# SignalAdapter.net
KiCad netlist of a schematic drawn in Altium Designer
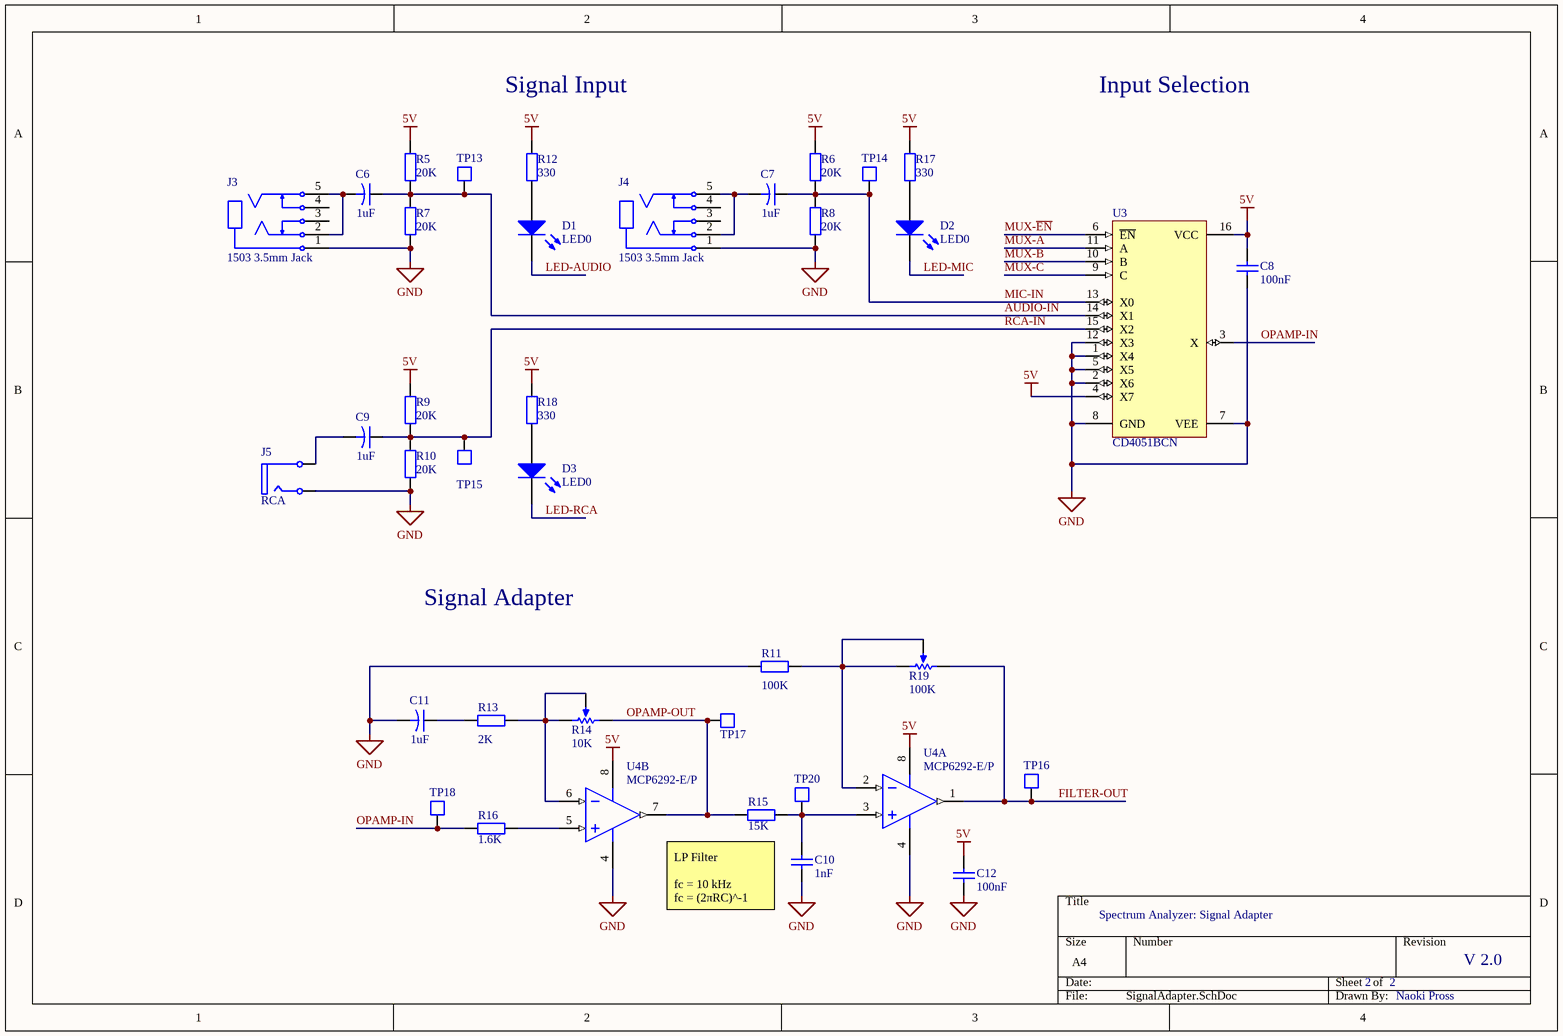
[diagram p0: SignalAdapter.SchDoc]

(export (version "E")
  (design (tool "Eeschema 10.0.6"))
  (components
    (comp (ref "C6")
      (value "1uF")
      (footprint "CAPR5-4X5")
      (description "Capacitor")
      (fields (field (name "Comment") "Cap2") (field (name "PUBLISHER") "Altium Limited"))
      (libsource (lib "Miscellaneous Devices") (part "Cap2"))
    )
    (comp (ref "C7")
      (value "1uF")
      (footprint "CAPR5-4X5")
      (description "Capacitor")
      (fields (field (name "Comment") "Cap2") (field (name "PUBLISHER") "Altium Limited"))
      (libsource (lib "Miscellaneous Devices") (part "Cap2"))
    )
    (comp (ref "C8")
      (value "100nF")
      (footprint "RAD-0.1")
      (description "Capacitor")
      (fields (field (name "Comment") "Cap") (field (name "PUBLISHER") "Altium Limited"))
      (libsource (lib "Miscellaneous Devices") (part "Cap"))
    )
    (comp (ref "C9")
      (value "1uF")
      (footprint "CAPR5-4X5")
      (description "Capacitor")
      (fields (field (name "Comment") "Cap2") (field (name "PUBLISHER") "Altium Limited"))
      (libsource (lib "Miscellaneous Devices") (part "Cap2"))
    )
    (comp (ref "C10")
      (value "1nF")
      (footprint "RAD-0.1")
      (description "Capacitor")
      (fields (field (name "Comment") "Cap") (field (name "PUBLISHER") "Altium Limited"))
      (libsource (lib "Miscellaneous Devices") (part "Cap"))
    )
    (comp (ref "C11")
      (value "1uF")
      (footprint "CAPR5-4X5")
      (description "Capacitor")
      (fields (field (name "Comment") "Cap2") (field (name "PUBLISHER") "Altium Limited"))
      (libsource (lib "Miscellaneous Devices") (part "Cap2"))
    )
    (comp (ref "C12")
      (value "100nF")
      (footprint "RAD-0.1")
      (description "Capacitor")
      (fields (field (name "Comment") "Cap") (field (name "PUBLISHER") "Altium Limited"))
      (libsource (lib "Miscellaneous Devices") (part "Cap"))
    )
    (comp (ref "D1")
      (value "LED0")
      (footprint "LED-0")
      (description "Typical INFRARED GaAs LED")
      (fields (field (name "PUBLISHER") "Altium Limited"))
      (libsource (lib "Miscellaneous Devices") (part "LED0"))
    )
    (comp (ref "D2")
      (value "LED0")
      (footprint "LED-0")
      (description "Typical INFRARED GaAs LED")
      (fields (field (name "PUBLISHER") "Altium Limited"))
      (libsource (lib "Miscellaneous Devices") (part "LED0"))
    )
    (comp (ref "D3")
      (value "LED0")
      (footprint "LED-0")
      (description "Typical INFRARED GaAs LED")
      (fields (field (name "PUBLISHER") "Altium Limited"))
      (libsource (lib "Miscellaneous Devices") (part "LED0"))
    )
    (comp (ref "J3")
      (value "1503 3.5mm Jack")
      (footprint "Lumberg-Connectors:JIS C 6560")
      (description "1503 09/17 Jack connector")
      (libsource (lib "lumberg-connectors") (part "1503"))
    )
    (comp (ref "J4")
      (value "1503 3.5mm Jack")
      (footprint "Lumberg-Connectors:JIS C 6560")
      (description "1503 09/17 Jack connector")
      (libsource (lib "lumberg-connectors") (part "1503"))
    )
    (comp (ref "J5")
      (value "RCA")
      (footprint "Lumberg-Connectors:RC-5231")
      (description "RCA Phono Jack, Right Angle, Thru-Hole, Snap-In")
      (fields (field (name "PUBLISHER") "Altium Limited"))
      (libsource (lib "Miscellaneous Connectors") (part "RCA"))
    )
    (comp (ref "R5")
      (value "20K")
      (footprint "AXIAL-0.4")
      (description "Resistor")
      (fields (field (name "Comment") "Res2") (field (name "PUBLISHER") "Altium Limited"))
      (libsource (lib "Miscellaneous Devices") (part "Res2"))
    )
    (comp (ref "R6")
      (value "20K")
      (footprint "AXIAL-0.4")
      (description "Resistor")
      (fields (field (name "Comment") "Res2") (field (name "PUBLISHER") "Altium Limited"))
      (libsource (lib "Miscellaneous Devices") (part "Res2"))
    )
    (comp (ref "R7")
      (value "20K")
      (footprint "AXIAL-0.4")
      (description "Resistor")
      (fields (field (name "Comment") "Res2") (field (name "PUBLISHER") "Altium Limited"))
      (libsource (lib "Miscellaneous Devices") (part "Res2"))
    )
    (comp (ref "R8")
      (value "20K")
      (footprint "AXIAL-0.4")
      (description "Resistor")
      (fields (field (name "Comment") "Res2") (field (name "PUBLISHER") "Altium Limited"))
      (libsource (lib "Miscellaneous Devices") (part "Res2"))
    )
    (comp (ref "R9")
      (value "20K")
      (footprint "AXIAL-0.4")
      (description "Resistor")
      (fields (field (name "Comment") "Res2") (field (name "PUBLISHER") "Altium Limited"))
      (libsource (lib "Miscellaneous Devices") (part "Res2"))
    )
    (comp (ref "R10")
      (value "20K")
      (footprint "AXIAL-0.4")
      (description "Resistor")
      (fields (field (name "Comment") "Res2") (field (name "PUBLISHER") "Altium Limited"))
      (libsource (lib "Miscellaneous Devices") (part "Res2"))
    )
    (comp (ref "R11")
      (value "100K")
      (footprint "AXIAL-0.4")
      (description "Resistor")
      (fields (field (name "Comment") "Res2") (field (name "PUBLISHER") "Altium Limited"))
      (libsource (lib "") (part "Res2_2"))
    )
    (comp (ref "R12")
      (value "330")
      (footprint "AXIAL-0.4")
      (description "Resistor")
      (fields (field (name "Comment") "Res2") (field (name "PUBLISHER") "Altium Limited"))
      (libsource (lib "Miscellaneous Devices") (part "Res2"))
    )
    (comp (ref "R13")
      (value "2K")
      (footprint "AXIAL-0.4")
      (description "Resistor")
      (fields (field (name "Comment") "Res2") (field (name "PUBLISHER") "Altium Limited"))
      (libsource (lib "") (part "Res2_2"))
    )
    (comp (ref "R14")
      (value "10K")
      (footprint "VR4")
      (description "Potentiometer")
      (fields (field (name "Comment") "RPot") (field (name "PUBLISHER") "Altium Limited"))
      (libsource (lib "Miscellaneous Devices") (part "RPot"))
    )
    (comp (ref "R15")
      (value "15K")
      (footprint "AXIAL-0.4")
      (description "Resistor")
      (fields (field (name "Comment") "Res2") (field (name "PUBLISHER") "Altium Limited"))
      (libsource (lib "") (part "Res2_1"))
    )
    (comp (ref "R16")
      (value "1.6K")
      (footprint "AXIAL-0.4")
      (description "Resistor")
      (fields (field (name "Comment") "Res2") (field (name "PUBLISHER") "Altium Limited"))
      (libsource (lib "") (part "Res2_1"))
    )
    (comp (ref "R17")
      (value "330")
      (footprint "AXIAL-0.4")
      (description "Resistor")
      (fields (field (name "Comment") "Res2") (field (name "PUBLISHER") "Altium Limited"))
      (libsource (lib "Miscellaneous Devices") (part "Res2"))
    )
    (comp (ref "R18")
      (value "330")
      (footprint "AXIAL-0.4")
      (description "Resistor")
      (fields (field (name "Comment") "Res2") (field (name "PUBLISHER") "Altium Limited"))
      (libsource (lib "Miscellaneous Devices") (part "Res2"))
    )
    (comp (ref "R19")
      (value "100K")
      (footprint "VR4")
      (description "Potentiometer")
      (fields (field (name "Comment") "RPot") (field (name "PUBLISHER") "Altium Limited"))
      (libsource (lib "Miscellaneous Devices") (part "RPot"))
    )
    (comp (ref "TP13") (value "Test Pad") (footprint "PIN1") (libsource (lib "TestPad") (part "TestPad")))
    (comp (ref "TP14") (value "Test Pad") (footprint "PIN1") (libsource (lib "TestPad") (part "TestPad")))
    (comp (ref "TP15") (value "Test Pad") (footprint "PIN1") (libsource (lib "TestPad") (part "TestPad")))
    (comp (ref "TP16") (value "Test Pad") (footprint "PIN1") (libsource (lib "TestPad") (part "TestPad")))
    (comp (ref "TP17") (value "Test Pad") (footprint "PIN1") (libsource (lib "TestPad") (part "TestPad")))
    (comp (ref "TP18") (value "Test Pad") (footprint "PIN1") (libsource (lib "TestPad") (part "TestPad")))
    (comp (ref "TP20") (value "Test Pad") (footprint "PIN1") (libsource (lib "TestPad") (part "TestPad")))
    (comp (ref "U3")
      (value "CD4051BCN")
      (footprint "N16E")
      (description "8-Channel Analog Multiplexer/Demultiplexer")
      (fields (field (name "PUBLISHER") "Altium Limited"))
      (libsource (lib "FSC Logic Multiplexer") (part "CD4051BCN"))
    )
    (comp (ref "U4")
      (value "MCP6292-E/P")
      (footprint "PDIP300-P8")
      (description "1.0 mA, 10 MHz Rail-to-Rail Operational Amplifier, 8-Pin PDIP, Extended Temperature")
      (fields (field (name "PUBLISHER") "Altium Limited"))
      (libsource (lib "Microchip Linear Devices") (part "MCP6292-E/P"))
    )
  )
  (nets
    (net (code "1") (name "/AUDIO-IN") (class "Default")
      (node (ref "C6") (pin "1") (pinfunction "1_1") (pintype "passive"))
      (node (ref "R5") (pin "1") (pinfunction "1_1") (pintype "passive"))
      (node (ref "R7") (pin "2") (pinfunction "2_2") (pintype "passive"))
      (node (ref "TP13") (pin "1") (pinfunction "1_1") (pintype "passive"))
      (node (ref "U3") (pin "14") (pinfunction "X1_14") (pintype "bidirectional"))
    )
    (net (code "2") (name "/FILTER-OUT") (class "Default")
      (node (ref "R19") (pin "1") (pinfunction "TOP_1") (pintype "passive"))
      (node (ref "TP16") (pin "1") (pinfunction "1_1") (pintype "passive"))
      (node (ref "U4") (pin "1") (pinfunction "VOUTA_1") (pintype "output"))
    )
    (net (code "3") (name "/LED-AUDIO") (class "Default")
      (node (ref "D1") (pin "2") (pinfunction "K_2") (pintype "passive"))
    )
    (net (code "4") (name "/LED-MIC") (class "Default")
      (node (ref "D2") (pin "2") (pinfunction "K_2") (pintype "passive"))
    )
    (net (code "5") (name "/LED-RCA") (class "Default")
      (node (ref "D3") (pin "2") (pinfunction "K_2") (pintype "passive"))
    )
    (net (code "6") (name "/MIC-IN") (class "Default")
      (node (ref "C7") (pin "1") (pinfunction "1_1") (pintype "passive"))
      (node (ref "R6") (pin "1") (pinfunction "1_1") (pintype "passive"))
      (node (ref "R8") (pin "2") (pinfunction "2_2") (pintype "passive"))
      (node (ref "TP14") (pin "1") (pinfunction "1_1") (pintype "passive"))
      (node (ref "U3") (pin "13") (pinfunction "X0_13") (pintype "bidirectional"))
    )
    (net (code "7") (name "/MUX-A") (class "Default")
      (node (ref "U3") (pin "11") (pinfunction "A_11") (pintype "input"))
    )
    (net (code "8") (name "/MUX-B") (class "Default")
      (node (ref "U3") (pin "10") (pinfunction "B_10") (pintype "input"))
    )
    (net (code "9") (name "/MUX-C") (class "Default")
      (node (ref "U3") (pin "9") (pinfunction "C_9") (pintype "input"))
    )
    (net (code "10") (name "/MUX-~{EN}") (class "Default")
      (node (ref "U3") (pin "6") (pinfunction "~{EN}_6") (pintype "input"))
    )
    (net (code "11") (name "/OPAMP-IN") (class "Default")
      (node (ref "R16") (pin "2") (pinfunction "2_2") (pintype "passive"))
      (node (ref "TP18") (pin "1") (pinfunction "1_1") (pintype "passive"))
      (node (ref "U3") (pin "3") (pinfunction "X_3") (pintype "bidirectional"))
    )
    (net (code "12") (name "/OPAMP-OUT") (class "Default")
      (node (ref "R14") (pin "1") (pinfunction "TOP_1") (pintype "passive"))
      (node (ref "R15") (pin "2") (pinfunction "2_2") (pintype "passive"))
      (node (ref "TP17") (pin "1") (pinfunction "1_1") (pintype "passive"))
      (node (ref "U4") (pin "7") (pinfunction "VOUTB_7") (pintype "output"))
    )
    (net (code "13") (name "/RCA-IN") (class "Default")
      (node (ref "C9") (pin "1") (pinfunction "1_1") (pintype "passive"))
      (node (ref "R10") (pin "2") (pinfunction "2_2") (pintype "passive"))
      (node (ref "R9") (pin "1") (pinfunction "1_1") (pintype "passive"))
      (node (ref "TP15") (pin "1") (pinfunction "1_1") (pintype "passive"))
      (node (ref "U3") (pin "15") (pinfunction "X2_15") (pintype "bidirectional"))
    )
    (net (code "14") (name "5V") (class "Default")
      (node (ref "C12") (pin "1") (pinfunction "1_1") (pintype "passive"))
      (node (ref "C8") (pin "1") (pinfunction "1_1") (pintype "passive"))
      (node (ref "R12") (pin "2") (pinfunction "2_2") (pintype "passive"))
      (node (ref "R17") (pin "2") (pinfunction "2_2") (pintype "passive"))
      (node (ref "R18") (pin "2") (pinfunction "2_2") (pintype "passive"))
      (node (ref "R5") (pin "2") (pinfunction "2_2") (pintype "passive"))
      (node (ref "R6") (pin "2") (pinfunction "2_2") (pintype "passive"))
      (node (ref "R9") (pin "2") (pinfunction "2_2") (pintype "passive"))
      (node (ref "U3") (pin "16") (pinfunction "VCC_16") (pintype "power_in"))
      (node (ref "U3") (pin "4") (pinfunction "X7_4") (pintype "bidirectional"))
      (node (ref "U4") (pin "8") (pinfunction "VDD_8") (pintype "power_in"))
    )
    (net (code "15") (name "GND") (class "Default")
      (node (ref "C10") (pin "1") (pinfunction "1_1") (pintype "passive"))
      (node (ref "C11") (pin "2") (pinfunction "2_2") (pintype "passive"))
      (node (ref "C12") (pin "2") (pinfunction "2_2") (pintype "passive"))
      (node (ref "C8") (pin "2") (pinfunction "2_2") (pintype "passive"))
      (node (ref "J3") (pin "1") (pinfunction "1_1") (pintype "passive"))
      (node (ref "J4") (pin "1") (pinfunction "1_1") (pintype "passive"))
      (node (ref "J5") (pin "2B") (pinfunction "Signal_2B") (pintype "passive"))
      (node (ref "R10") (pin "1") (pinfunction "1_1") (pintype "passive"))
      (node (ref "R11") (pin "1") (pinfunction "1_1") (pintype "passive"))
      (node (ref "R7") (pin "1") (pinfunction "1_1") (pintype "passive"))
      (node (ref "R8") (pin "1") (pinfunction "1_1") (pintype "passive"))
      (node (ref "U3") (pin "1") (pinfunction "X4_1") (pintype "bidirectional"))
      (node (ref "U3") (pin "12") (pinfunction "X3_12") (pintype "bidirectional"))
      (node (ref "U3") (pin "2") (pinfunction "X6_2") (pintype "bidirectional"))
      (node (ref "U3") (pin "5") (pinfunction "X5_5") (pintype "bidirectional"))
      (node (ref "U3") (pin "7") (pinfunction "VEE_7") (pintype "power_in"))
      (node (ref "U3") (pin "8") (pinfunction "GND_8") (pintype "power_in"))
      (node (ref "U4") (pin "4") (pinfunction "VSS_4") (pintype "power_in"))
    )
    (net (code "16") (name "Net-(C6-Pad2)") (class "Default")
      (node (ref "C6") (pin "2") (pinfunction "2_2") (pintype "passive"))
      (node (ref "J3") (pin "2") (pinfunction "2_2") (pintype "passive"))
      (node (ref "J3") (pin "5") (pinfunction "5_5") (pintype "passive"))
    )
    (net (code "17") (name "Net-(C7-Pad2)") (class "Default")
      (node (ref "C7") (pin "2") (pinfunction "2_2") (pintype "passive"))
      (node (ref "J4") (pin "2") (pinfunction "2_2") (pintype "passive"))
      (node (ref "J4") (pin "5") (pinfunction "5_5") (pintype "passive"))
    )
    (net (code "18") (name "Net-(C11-Pad1)") (class "Default")
      (node (ref "C11") (pin "1") (pinfunction "1_1") (pintype "passive"))
      (node (ref "R13") (pin "1") (pinfunction "1_1") (pintype "passive"))
    )
    (net (code "19") (name "Net-(D1-A)") (class "Default")
      (node (ref "D1") (pin "1") (pinfunction "A_1") (pintype "passive"))
      (node (ref "R12") (pin "1") (pinfunction "1_1") (pintype "passive"))
    )
    (net (code "20") (name "Net-(D2-A)") (class "Default")
      (node (ref "D2") (pin "1") (pinfunction "A_1") (pintype "passive"))
      (node (ref "R17") (pin "1") (pinfunction "1_1") (pintype "passive"))
    )
    (net (code "21") (name "Net-(D3-A)") (class "Default")
      (node (ref "D3") (pin "1") (pinfunction "A_1") (pintype "passive"))
      (node (ref "R18") (pin "1") (pinfunction "1_1") (pintype "passive"))
    )
    (net (code "22") (name "Net-(J5-Ground)") (class "Default")
      (node (ref "C9") (pin "2") (pinfunction "2_2") (pintype "passive"))
      (node (ref "J5") (pin "1A") (pinfunction "Ground_1A") (pintype "power_in"))
    )
    (net (code "23") (name "Net-(R14-BOT)") (class "Default")
      (node (ref "R13") (pin "2") (pinfunction "2_2") (pintype "passive"))
      (node (ref "R14") (pin "2") (pinfunction "BOT_2") (pintype "passive"))
      (node (ref "R14") (pin "3") (pinfunction "TAP_3") (pintype "passive"))
      (node (ref "U4") (pin "6") (pinfunction "VINB-_6") (pintype "input"))
    )
    (net (code "24") (name "Net-(R19-BOT)") (class "Default")
      (node (ref "R11") (pin "2") (pinfunction "2_2") (pintype "passive"))
      (node (ref "R19") (pin "2") (pinfunction "BOT_2") (pintype "passive"))
      (node (ref "R19") (pin "3") (pinfunction "TAP_3") (pintype "passive"))
      (node (ref "U4") (pin "2") (pinfunction "VINA-_2") (pintype "input"))
    )
    (net (code "25") (name "Net-(U4A-VINA+)") (class "Default")
      (node (ref "C10") (pin "2") (pinfunction "2_2") (pintype "passive"))
      (node (ref "R15") (pin "1") (pinfunction "1_1") (pintype "passive"))
      (node (ref "TP20") (pin "1") (pinfunction "1_1") (pintype "passive"))
      (node (ref "U4") (pin "3") (pinfunction "VINA+_3") (pintype "input"))
    )
    (net (code "26") (name "Net-(U4B-VINB+)") (class "Default")
      (node (ref "R16") (pin "1") (pinfunction "1_1") (pintype "passive"))
      (node (ref "U4") (pin "5") (pinfunction "VINB+_5") (pintype "input"))
    )
    (net (code "27") (name "unconnected-(J3-Pad3)") (class "Default")
      (node (ref "J3") (pin "3") (pinfunction "3_3") (pintype "passive"))
    )
    (net (code "28") (name "unconnected-(J3-Pad4)") (class "Default")
      (node (ref "J3") (pin "4") (pinfunction "4_4") (pintype "passive"))
    )
    (net (code "29") (name "unconnected-(J4-Pad3)") (class "Default")
      (node (ref "J4") (pin "3") (pinfunction "3_3") (pintype "passive"))
    )
    (net (code "30") (name "unconnected-(J4-Pad4)") (class "Default")
      (node (ref "J4") (pin "4") (pinfunction "4_4") (pintype "passive"))
    )
  )
)
